# 780-00033_rev_4_486_CCD_Interface.net
KiCad netlist of a schematic drawn in Altium Designer
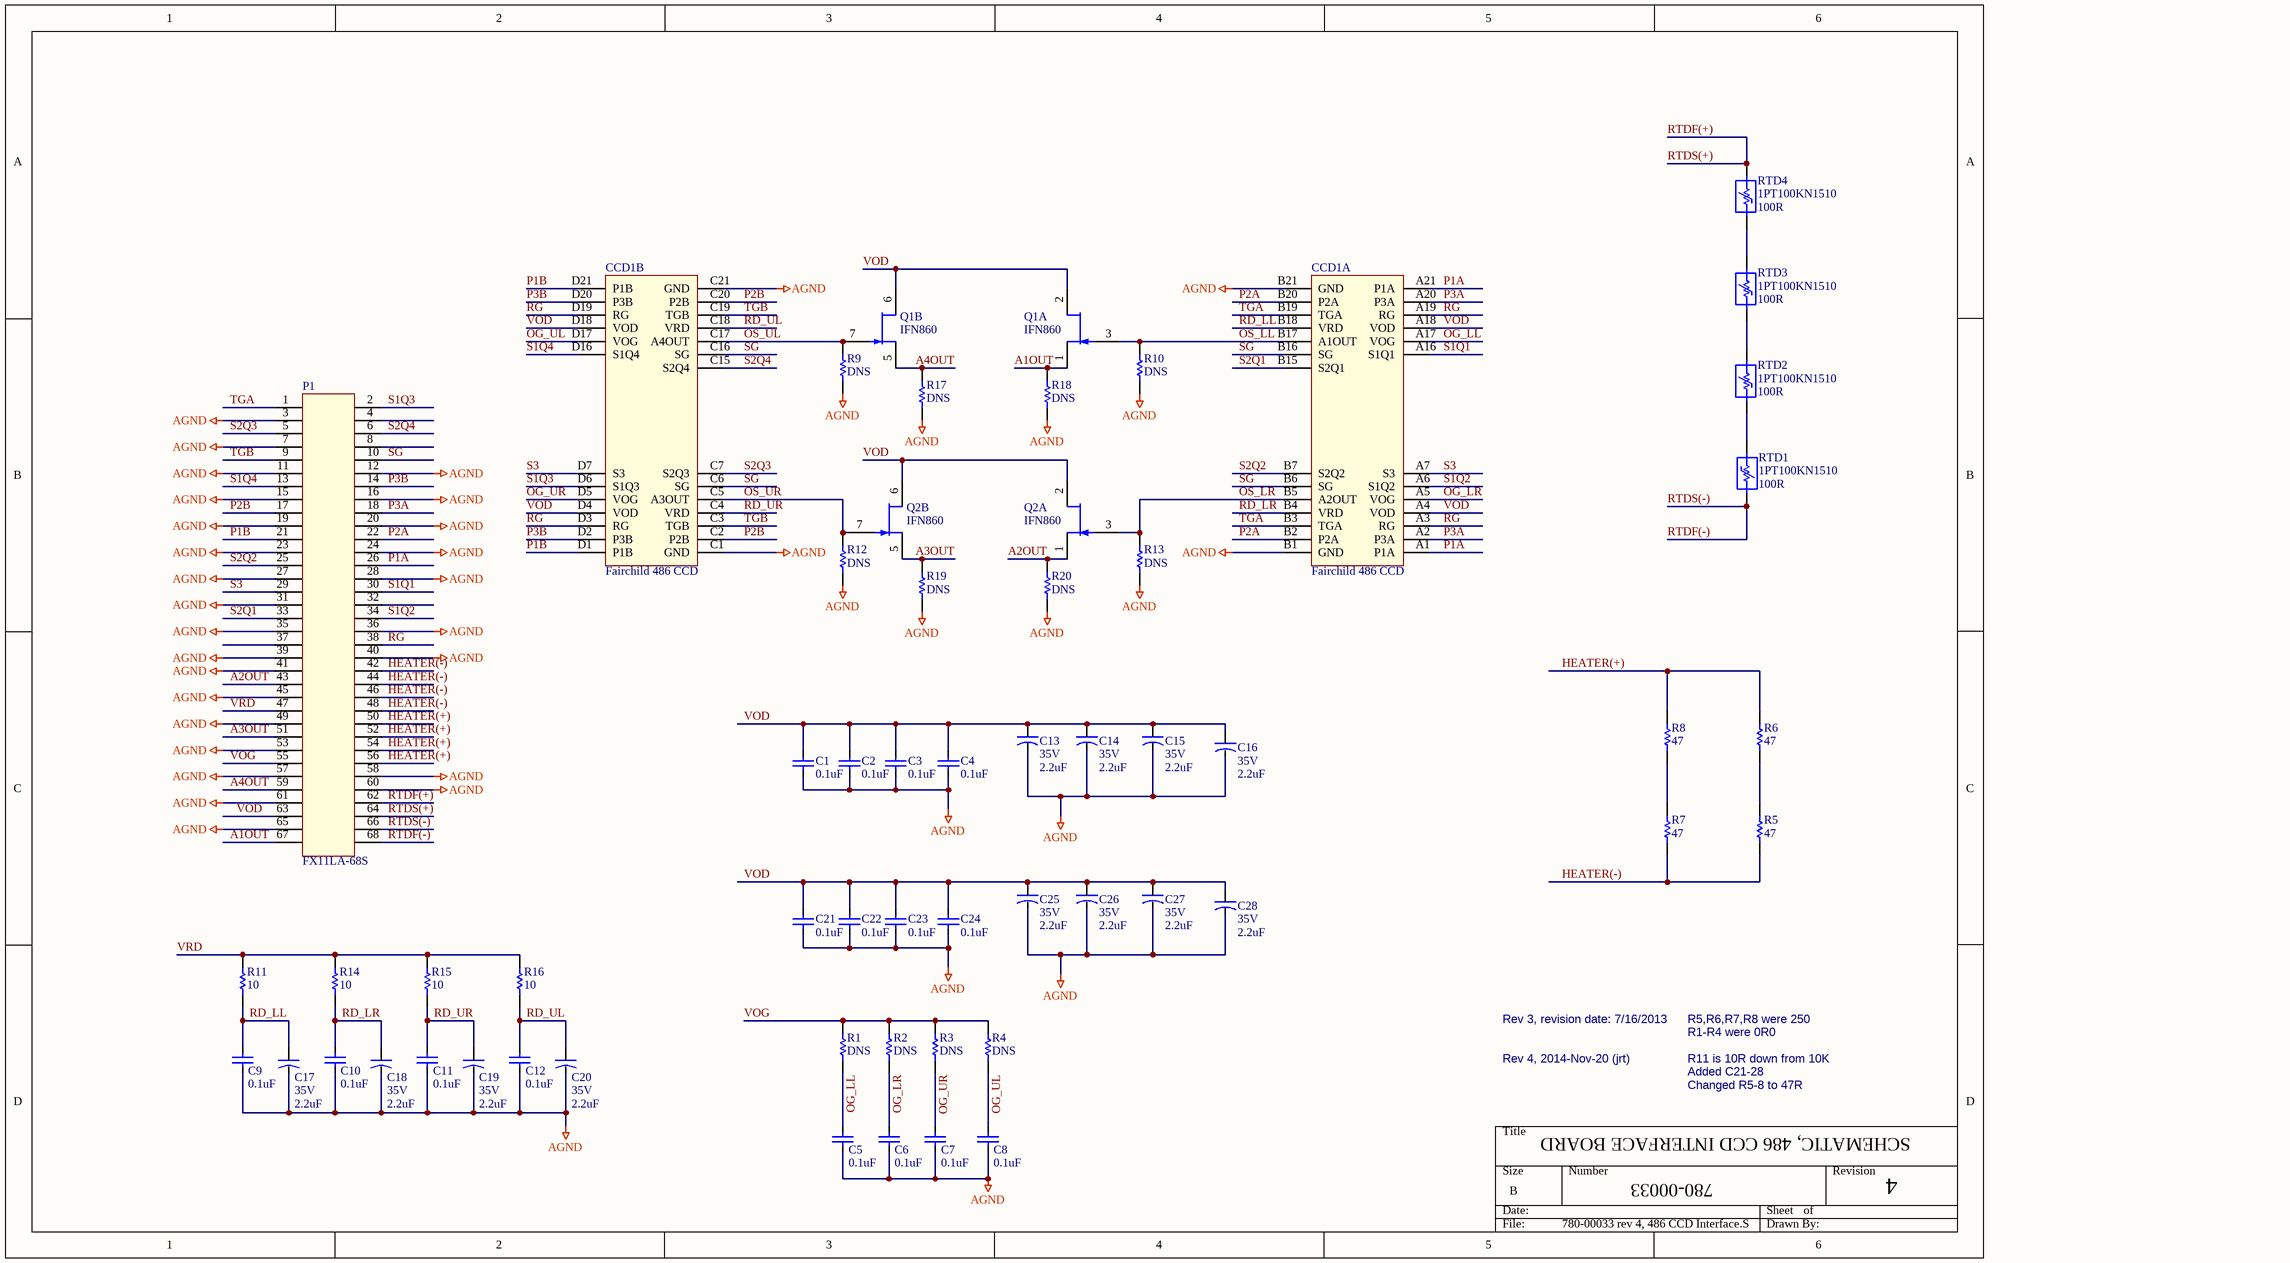
[diagram p0: 780-00033 rev 4, 486 CCD Interface.SchDoc]

(export (version "E")
  (design (tool "Eeschema 10.0.6"))
  (components
    (comp (ref "C1")
      (value "0.1uF")
      (footprint "SMD_0805")
      (description "Capacitor")
      (fields (field (name "MANUFACTURER") "AVX") (field (name "Comment") "Cap SMD"))
      (libsource (lib "175-00029, rev3, 486 CCD Interface") (part "Cap SMD"))
    )
    (comp (ref "C2")
      (value "0.1uF")
      (footprint "SMD_0805")
      (description "Capacitor")
      (fields (field (name "MANUFACTURER") "AVX") (field (name "Comment") "Cap SMD"))
      (libsource (lib "175-00029, rev3, 486 CCD Interface") (part "Cap SMD"))
    )
    (comp (ref "C3")
      (value "0.1uF")
      (footprint "SMD_0805")
      (description "Capacitor")
      (fields (field (name "MANUFACTURER") "AVX") (field (name "Comment") "Cap SMD"))
      (libsource (lib "175-00029, rev3, 486 CCD Interface") (part "Cap SMD"))
    )
    (comp (ref "C4")
      (value "0.1uF")
      (footprint "SMD_0805")
      (description "Capacitor")
      (fields (field (name "MANUFACTURER") "AVX") (field (name "Comment") "Cap SMD"))
      (libsource (lib "175-00029, rev3, 486 CCD Interface") (part "Cap SMD"))
    )
    (comp (ref "C5")
      (value "0.1uF")
      (footprint "SMD_0805")
      (description "Capacitor")
      (fields (field (name "MANUFACTURER") "AVX") (field (name "Comment") "Cap SMD"))
      (libsource (lib "175-00029, rev3, 486 CCD Interface") (part "Cap SMD"))
    )
    (comp (ref "C6")
      (value "0.1uF")
      (footprint "SMD_0805")
      (description "Capacitor")
      (fields (field (name "MANUFACTURER") "AVX") (field (name "Comment") "Cap SMD"))
      (libsource (lib "175-00029, rev3, 486 CCD Interface") (part "Cap SMD"))
    )
    (comp (ref "C7")
      (value "0.1uF")
      (footprint "SMD_0805")
      (description "Capacitor")
      (fields (field (name "MANUFACTURER") "AVX") (field (name "Comment") "Cap SMD"))
      (libsource (lib "175-00029, rev3, 486 CCD Interface") (part "Cap SMD"))
    )
    (comp (ref "C8")
      (value "0.1uF")
      (footprint "SMD_0805")
      (description "Capacitor")
      (fields (field (name "MANUFACTURER") "AVX") (field (name "Comment") "Cap SMD"))
      (libsource (lib "175-00029, rev3, 486 CCD Interface") (part "Cap SMD"))
    )
    (comp (ref "C9")
      (value "0.1uF")
      (footprint "SMD_0805")
      (description "Capacitor")
      (fields (field (name "MANUFACTURER") "AVX") (field (name "Comment") "Cap SMD"))
      (libsource (lib "175-00029, rev3, 486 CCD Interface") (part "Cap SMD"))
    )
    (comp (ref "C10")
      (value "0.1uF")
      (footprint "SMD_0805")
      (description "Capacitor")
      (fields (field (name "MANUFACTURER") "AVX") (field (name "Comment") "Cap SMD"))
      (libsource (lib "175-00029, rev3, 486 CCD Interface") (part "Cap SMD"))
    )
    (comp (ref "C11")
      (value "0.1uF")
      (footprint "SMD_0805")
      (description "Capacitor")
      (fields (field (name "MANUFACTURER") "AVX") (field (name "Comment") "Cap SMD"))
      (libsource (lib "175-00029, rev3, 486 CCD Interface") (part "Cap SMD"))
    )
    (comp (ref "C12")
      (value "0.1uF")
      (footprint "SMD_0805")
      (description "Capacitor")
      (fields (field (name "MANUFACTURER") "AVX") (field (name "Comment") "Cap SMD"))
      (libsource (lib "175-00029, rev3, 486 CCD Interface") (part "Cap SMD"))
    )
    (comp (ref "C13")
      (value "35V")
      (footprint "SMD_CAP_3216")
      (description "outline 3.2mm x 1.6 mm, 1206")
      (fields (field (name "MANUFACTURER") "AVX") (field (name "ALTIUM_VALUE") "2.2uF"))
      (libsource (lib "175-00029, rev3, 486 CCD Interface") (part "Cap 2.2uF 35V Low ESR"))
    )
    (comp (ref "C14")
      (value "35V")
      (footprint "SMD_CAP_3216")
      (description "outline 3.2mm x 1.6 mm, 1206")
      (fields (field (name "MANUFACTURER") "AVX") (field (name "ALTIUM_VALUE") "2.2uF"))
      (libsource (lib "175-00029, rev3, 486 CCD Interface") (part "Cap 2.2uF 35V Low ESR"))
    )
    (comp (ref "C15")
      (value "35V")
      (footprint "SMD_CAP_3216")
      (description "outline 3.2mm x 1.6 mm, 1206")
      (fields (field (name "MANUFACTURER") "AVX") (field (name "ALTIUM_VALUE") "2.2uF"))
      (libsource (lib "175-00029, rev3, 486 CCD Interface") (part "Cap 2.2uF 35V Low ESR"))
    )
    (comp (ref "C16")
      (value "35V")
      (footprint "SMD_CAP_3216")
      (description "outline 3.2mm x 1.6 mm, 1206")
      (fields (field (name "MANUFACTURER") "AVX") (field (name "ALTIUM_VALUE") "2.2uF"))
      (libsource (lib "175-00029, rev3, 486 CCD Interface") (part "Cap 2.2uF 35V Low ESR"))
    )
    (comp (ref "C17")
      (value "35V")
      (footprint "SMD_CAP_3216")
      (description "outline 3.2mm x 1.6 mm, 1206")
      (fields (field (name "MANUFACTURER") "AVX") (field (name "ALTIUM_VALUE") "2.2uF"))
      (libsource (lib "175-00029, rev3, 486 CCD Interface") (part "Cap 2.2uF 35V Low ESR"))
    )
    (comp (ref "C18")
      (value "35V")
      (footprint "SMD_CAP_3216")
      (description "outline 3.2mm x 1.6 mm, 1206")
      (fields (field (name "MANUFACTURER") "AVX") (field (name "ALTIUM_VALUE") "2.2uF"))
      (libsource (lib "175-00029, rev3, 486 CCD Interface") (part "Cap 2.2uF 35V Low ESR"))
    )
    (comp (ref "C19")
      (value "35V")
      (footprint "SMD_CAP_3216")
      (description "outline 3.2mm x 1.6 mm, 1206")
      (fields (field (name "MANUFACTURER") "AVX") (field (name "ALTIUM_VALUE") "2.2uF"))
      (libsource (lib "175-00029, rev3, 486 CCD Interface") (part "Cap 2.2uF 35V Low ESR"))
    )
    (comp (ref "C20")
      (value "35V")
      (footprint "SMD_CAP_3216")
      (description "outline 3.2mm x 1.6 mm, 1206")
      (fields (field (name "MANUFACTURER") "AVX") (field (name "ALTIUM_VALUE") "2.2uF"))
      (libsource (lib "175-00029, rev3, 486 CCD Interface") (part "Cap 2.2uF 35V Low ESR"))
    )
    (comp (ref "C21")
      (value "0.1uF")
      (footprint "SMD_0805")
      (description "Capacitor")
      (fields (field (name "MANUFACTURER") "AVX"))
      (libsource (lib "175-00029, rev3, 486 CCD Interface") (part "Cap SMD"))
    )
    (comp (ref "C22")
      (value "0.1uF")
      (footprint "SMD_0805")
      (description "Capacitor")
      (fields (field (name "MANUFACTURER") "AVX"))
      (libsource (lib "175-00029, rev3, 486 CCD Interface") (part "Cap SMD"))
    )
    (comp (ref "C23")
      (value "0.1uF")
      (footprint "SMD_0805")
      (description "Capacitor")
      (fields (field (name "MANUFACTURER") "AVX") (field (name "Comment") "Cap SMD"))
      (libsource (lib "175-00029, rev3, 486 CCD Interface") (part "Cap SMD"))
    )
    (comp (ref "C24")
      (value "0.1uF")
      (footprint "SMD_0805")
      (description "Capacitor")
      (fields (field (name "MANUFACTURER") "AVX") (field (name "Comment") "Cap SMD"))
      (libsource (lib "175-00029, rev3, 486 CCD Interface") (part "Cap SMD"))
    )
    (comp (ref "C25")
      (value "35V")
      (footprint "SMD_CAP_3216")
      (description "outline 3.2mm x 1.6 mm, 1206")
      (fields (field (name "MANUFACTURER") "AVX") (field (name "ALTIUM_VALUE") "2.2uF"))
      (libsource (lib "175-00029, rev3, 486 CCD Interface") (part "Cap 2.2uF 35V Low ESR"))
    )
    (comp (ref "C26")
      (value "35V")
      (footprint "SMD_CAP_3216")
      (description "outline 3.2mm x 1.6 mm, 1206")
      (fields (field (name "MANUFACTURER") "AVX") (field (name "ALTIUM_VALUE") "2.2uF"))
      (libsource (lib "175-00029, rev3, 486 CCD Interface") (part "Cap 2.2uF 35V Low ESR"))
    )
    (comp (ref "C27")
      (value "35V")
      (footprint "SMD_CAP_3216")
      (description "outline 3.2mm x 1.6 mm, 1206")
      (fields (field (name "MANUFACTURER") "AVX") (field (name "ALTIUM_VALUE") "2.2uF"))
      (libsource (lib "175-00029, rev3, 486 CCD Interface") (part "Cap 2.2uF 35V Low ESR"))
    )
    (comp (ref "C28")
      (value "35V")
      (footprint "SMD_CAP_3216")
      (description "outline 3.2mm x 1.6 mm, 1206")
      (fields (field (name "MANUFACTURER") "AVX") (field (name "ALTIUM_VALUE") "2.2uF"))
      (libsource (lib "175-00029, rev3, 486 CCD Interface") (part "Cap 2.2uF 35V Low ESR"))
    )
    (comp (ref "CCD1")
      (value "Fairchild 486 CCD")
      (footprint "Fairchild 486")
      (libsource (lib "175-00029, rev3, 486 CCD Interface") (part "Fairchild 486 CCD"))
    )
    (comp (ref "P1")
      (value "FX11LA-68S")
      (description "HIROSE 68P Receptacle")
      (fields (field (name "MANUFACTURER") "HiRose"))
      (libsource (lib "175-00029, rev3, 486 CCD Interface") (part "FX11LA-68S"))
    )
    (comp (ref "Q1")
      (value "IFN860")
      (footprint "TO-71")
      (description "N-JFET NJ450L Process")
      (fields (field (name "MANUFACTURER") "INTERFET"))
      (libsource (lib "175-00029, rev3, 486 CCD Interface") (part "IFN860"))
    )
    (comp (ref "Q2")
      (value "IFN860")
      (footprint "TO-71")
      (description "N-JFET NJ450L Process")
      (fields (field (name "MANUFACTURER") "INTERFET"))
      (libsource (lib "175-00029, rev3, 486 CCD Interface") (part "IFN860"))
    )
    (comp (ref "R1")
      (value "DNS")
      (footprint "SMD_0805")
      (description "Resistor 0805")
      (fields (field (name "Comment") "Res SMD"))
      (libsource (lib "175-00029, rev3, 486 CCD Interface") (part "Res SMD"))
    )
    (comp (ref "R2")
      (value "DNS")
      (footprint "SMD_0805")
      (description "Resistor 0805")
      (fields (field (name "Comment") "Res SMD"))
      (libsource (lib "175-00029, rev3, 486 CCD Interface") (part "Res SMD"))
    )
    (comp (ref "R3")
      (value "DNS")
      (footprint "SMD_0805")
      (description "Resistor 0805")
      (fields (field (name "Comment") "Res SMD"))
      (libsource (lib "175-00029, rev3, 486 CCD Interface") (part "Res SMD"))
    )
    (comp (ref "R4")
      (value "DNS")
      (footprint "SMD_0805")
      (description "Resistor 0805")
      (fields (field (name "Comment") "Res SMD"))
      (libsource (lib "175-00029, rev3, 486 CCD Interface") (part "Res SMD"))
    )
    (comp (ref "R5")
      (value "47")
      (footprint "AXIAL-0.5")
      (description "Resistor")
      (fields (field (name "MANUFACTURER") "Vishay/Dale") (field (name "Comment") "Res TH"))
      (libsource (lib "175-00029, rev3, 486 CCD Interface") (part "Res TH"))
    )
    (comp (ref "R6")
      (value "47")
      (footprint "AXIAL-0.5")
      (description "Resistor")
      (fields (field (name "MANUFACTURER") "Vishay/Dale") (field (name "Comment") "Res TH"))
      (libsource (lib "175-00029, rev3, 486 CCD Interface") (part "Res TH"))
    )
    (comp (ref "R7")
      (value "47")
      (footprint "AXIAL-0.5")
      (description "Resistor")
      (fields (field (name "MANUFACTURER") "Vishay/Dale") (field (name "Comment") "Res TH"))
      (libsource (lib "175-00029, rev3, 486 CCD Interface") (part "Res TH"))
    )
    (comp (ref "R8")
      (value "47")
      (footprint "AXIAL-0.5")
      (description "Resistor")
      (fields (field (name "MANUFACTURER") "Vishay/Dale") (field (name "Comment") "Res TH"))
      (libsource (lib "175-00029, rev3, 486 CCD Interface") (part "Res TH"))
    )
    (comp (ref "R9")
      (value "DNS")
      (footprint "SMD_0805")
      (description "Resistor 0805")
      (fields (field (name "Comment") "Res SMD"))
      (libsource (lib "175-00029, rev3, 486 CCD Interface") (part "Res SMD"))
    )
    (comp (ref "R10")
      (value "DNS")
      (footprint "SMD_0805")
      (description "Resistor 0805")
      (fields (field (name "Comment") "Res SMD"))
      (libsource (lib "175-00029, rev3, 486 CCD Interface") (part "Res SMD"))
    )
    (comp (ref "R11")
      (value "10")
      (footprint "SMD_0805")
      (description "Resistor 0805")
      (fields (field (name "Comment") "Res SMD"))
      (libsource (lib "175-00029, rev3, 486 CCD Interface") (part "Res SMD"))
    )
    (comp (ref "R12")
      (value "DNS")
      (footprint "SMD_0805")
      (description "Resistor 0805")
      (fields (field (name "Comment") "Res SMD"))
      (libsource (lib "175-00029, rev3, 486 CCD Interface") (part "Res SMD"))
    )
    (comp (ref "R13")
      (value "DNS")
      (footprint "SMD_0805")
      (description "Resistor 0805")
      (fields (field (name "Comment") "Res SMD"))
      (libsource (lib "175-00029, rev3, 486 CCD Interface") (part "Res SMD"))
    )
    (comp (ref "R14")
      (value "10")
      (footprint "SMD_0805")
      (description "Resistor 0805")
      (fields (field (name "Comment") "Res SMD"))
      (libsource (lib "175-00029, rev3, 486 CCD Interface") (part "Res SMD"))
    )
    (comp (ref "R15")
      (value "10")
      (footprint "SMD_0805")
      (description "Resistor 0805")
      (fields (field (name "Comment") "Res SMD"))
      (libsource (lib "175-00029, rev3, 486 CCD Interface") (part "Res SMD"))
    )
    (comp (ref "R16")
      (value "10")
      (footprint "SMD_0805")
      (description "Resistor 0805")
      (fields (field (name "Comment") "Res SMD"))
      (libsource (lib "175-00029, rev3, 486 CCD Interface") (part "Res SMD"))
    )
    (comp (ref "R17")
      (value "DNS")
      (footprint "SMD_0805")
      (description "Resistor 0805")
      (fields (field (name "Comment") "Res SMD"))
      (libsource (lib "175-00029, rev3, 486 CCD Interface") (part "Res SMD"))
    )
    (comp (ref "R18")
      (value "DNS")
      (footprint "SMD_0805")
      (description "Resistor 0805")
      (fields (field (name "Comment") "Res SMD"))
      (libsource (lib "175-00029, rev3, 486 CCD Interface") (part "Res SMD"))
    )
    (comp (ref "R19")
      (value "DNS")
      (footprint "SMD_0805")
      (description "Resistor 0805")
      (fields (field (name "Comment") "Res SMD"))
      (libsource (lib "175-00029, rev3, 486 CCD Interface") (part "Res SMD"))
    )
    (comp (ref "R20")
      (value "DNS")
      (footprint "SMD_0805")
      (description "Resistor 0805")
      (fields (field (name "Comment") "Res SMD"))
      (libsource (lib "175-00029, rev3, 486 CCD Interface") (part "Res SMD"))
    )
    (comp (ref "RTD1")
      (value "100R")
      (footprint "RTD 1x15mm")
      (description "Pt RTD")
      (fields
        (field (name "MANUFACTURER") "OMEGA")
        (field (name "MANUF P/N") "1PT100KN1510")
        (field (name "Comment") "RTD 2-wire, 1x15mm")
      )
      (libsource (lib "175-00029, rev3, 486 CCD Interface") (part "RTD 2-wire, 1x15mm"))
    )
    (comp (ref "RTD2")
      (value "100R")
      (footprint "RTD 1x15mm")
      (description "Pt RTD")
      (fields
        (field (name "MANUFACTURER") "OMEGA")
        (field (name "MANUF P/N") "1PT100KN1510")
        (field (name "Comment") "RTD 2-wire, 1x15mm")
      )
      (libsource (lib "175-00029, rev3, 486 CCD Interface") (part "RTD 2-wire, 1x15mm"))
    )
    (comp (ref "RTD3")
      (value "100R")
      (footprint "RTD 1x15mm")
      (description "Pt RTD")
      (fields
        (field (name "MANUFACTURER") "OMEGA")
        (field (name "MANUF P/N") "1PT100KN1510")
        (field (name "Comment") "RTD 2-wire, 1x15mm")
      )
      (libsource (lib "175-00029, rev3, 486 CCD Interface") (part "RTD 2-wire, 1x15mm"))
    )
    (comp (ref "RTD4")
      (value "100R")
      (footprint "RTD 1x15mm")
      (description "Pt RTD")
      (fields
        (field (name "MANUFACTURER") "OMEGA")
        (field (name "MANUF P/N") "1PT100KN1510")
        (field (name "Comment") "RTD 2-wire, 1x15mm")
      )
      (libsource (lib "175-00029, rev3, 486 CCD Interface") (part "RTD 2-wire, 1x15mm"))
    )
  )
  (nets
    (net (code "1") (name "/A1OUT") (class "Default")
      (node (ref "P1") (pin "67") (pintype "passive"))
      (node (ref "Q1") (pin "1") (pinfunction "S_1") (pintype "passive"))
      (node (ref "R18") (pin "1") (pinfunction "1_1") (pintype "passive"))
    )
    (net (code "2") (name "/A2OUT") (class "Default")
      (node (ref "P1") (pin "43") (pintype "passive"))
      (node (ref "Q2") (pin "1") (pinfunction "S_1") (pintype "passive"))
      (node (ref "R20") (pin "1") (pinfunction "1_1") (pintype "passive"))
    )
    (net (code "3") (name "/A3OUT") (class "Default")
      (node (ref "P1") (pin "51") (pintype "passive"))
      (node (ref "Q2") (pin "5") (pinfunction "S_5") (pintype "passive"))
      (node (ref "R19") (pin "1") (pinfunction "1_1") (pintype "passive"))
    )
    (net (code "4") (name "/A4OUT") (class "Default")
      (node (ref "P1") (pin "59") (pintype "passive"))
      (node (ref "Q1") (pin "5") (pinfunction "S_5") (pintype "passive"))
      (node (ref "R17") (pin "1") (pinfunction "1_1") (pintype "passive"))
    )
    (net (code "5") (name "/HEATER(+)") (class "Default")
      (node (ref "P1") (pin "50") (pintype "passive"))
      (node (ref "P1") (pin "52") (pintype "passive"))
      (node (ref "P1") (pin "54") (pintype "passive"))
      (node (ref "P1") (pin "56") (pintype "passive"))
      (node (ref "R6") (pin "1") (pinfunction "1_1") (pintype "passive"))
      (node (ref "R8") (pin "2") (pinfunction "2_2") (pintype "passive"))
    )
    (net (code "6") (name "/HEATER(-)") (class "Default")
      (node (ref "P1") (pin "42") (pintype "passive"))
      (node (ref "P1") (pin "44") (pintype "passive"))
      (node (ref "P1") (pin "46") (pintype "passive"))
      (node (ref "P1") (pin "48") (pintype "passive"))
      (node (ref "R5") (pin "1") (pinfunction "1_1") (pintype "passive"))
      (node (ref "R7") (pin "2") (pinfunction "2_2") (pintype "passive"))
    )
    (net (code "7") (name "/OG_LL") (class "Default")
      (node (ref "C5") (pin "2") (pinfunction "2_2") (pintype "passive"))
      (node (ref "CCD1") (pin "A17") (pinfunction "VOG_A17") (pintype "passive"))
      (node (ref "R1") (pin "1") (pinfunction "1_1") (pintype "passive"))
    )
    (net (code "8") (name "/OG_LR") (class "Default")
      (node (ref "C6") (pin "2") (pinfunction "2_2") (pintype "passive"))
      (node (ref "CCD1") (pin "A5") (pinfunction "VOG_A5") (pintype "passive"))
      (node (ref "R2") (pin "1") (pinfunction "1_1") (pintype "passive"))
    )
    (net (code "9") (name "/OG_UL") (class "Default")
      (node (ref "C8") (pin "2") (pinfunction "2_2") (pintype "passive"))
      (node (ref "CCD1") (pin "D17") (pinfunction "VOG_D17") (pintype "passive"))
      (node (ref "R4") (pin "1") (pinfunction "1_1") (pintype "passive"))
    )
    (net (code "10") (name "/OG_UR") (class "Default")
      (node (ref "C7") (pin "2") (pinfunction "2_2") (pintype "passive"))
      (node (ref "CCD1") (pin "D5") (pinfunction "VOG_D5") (pintype "passive"))
      (node (ref "R3") (pin "1") (pinfunction "1_1") (pintype "passive"))
    )
    (net (code "11") (name "/OS_LL") (class "Default")
      (node (ref "CCD1") (pin "B17") (pinfunction "A1OUT_B17") (pintype "passive"))
      (node (ref "Q1") (pin "3") (pinfunction "G_3") (pintype "passive"))
      (node (ref "R10") (pin "2") (pinfunction "2_2") (pintype "passive"))
    )
    (net (code "12") (name "/OS_LR") (class "Default")
      (node (ref "CCD1") (pin "B5") (pinfunction "A2OUT_B5") (pintype "passive"))
      (node (ref "Q2") (pin "3") (pinfunction "G_3") (pintype "passive"))
      (node (ref "R13") (pin "2") (pinfunction "2_2") (pintype "passive"))
    )
    (net (code "13") (name "/OS_UL") (class "Default")
      (node (ref "CCD1") (pin "C17") (pinfunction "A4OUT_C17") (pintype "passive"))
      (node (ref "Q1") (pin "7") (pinfunction "G_7") (pintype "passive"))
      (node (ref "R9") (pin "2") (pinfunction "2_2") (pintype "passive"))
    )
    (net (code "14") (name "/OS_UR") (class "Default")
      (node (ref "CCD1") (pin "C5") (pinfunction "A3OUT_C5") (pintype "passive"))
      (node (ref "Q2") (pin "7") (pinfunction "G_7") (pintype "passive"))
      (node (ref "R12") (pin "2") (pinfunction "2_2") (pintype "passive"))
    )
    (net (code "15") (name "/P1A") (class "Default")
      (node (ref "CCD1") (pin "A1") (pinfunction "P1A_A1") (pintype "passive"))
      (node (ref "CCD1") (pin "A21") (pinfunction "P1A_A21") (pintype "passive"))
      (node (ref "P1") (pin "26") (pintype "passive"))
    )
    (net (code "16") (name "/P1B") (class "Default")
      (node (ref "CCD1") (pin "D1") (pinfunction "P1B_D1") (pintype "passive"))
      (node (ref "CCD1") (pin "D21") (pinfunction "P1B_D21") (pintype "passive"))
      (node (ref "P1") (pin "21") (pintype "passive"))
    )
    (net (code "17") (name "/P2A") (class "Default")
      (node (ref "CCD1") (pin "B2") (pinfunction "P2A_B2") (pintype "passive"))
      (node (ref "CCD1") (pin "B20") (pinfunction "P2A_B20") (pintype "passive"))
      (node (ref "P1") (pin "22") (pintype "passive"))
    )
    (net (code "18") (name "/P2B") (class "Default")
      (node (ref "CCD1") (pin "C2") (pinfunction "P2B_C2") (pintype "passive"))
      (node (ref "CCD1") (pin "C20") (pinfunction "P2B_C20") (pintype "passive"))
      (node (ref "P1") (pin "17") (pintype "passive"))
    )
    (net (code "19") (name "/P3A") (class "Default")
      (node (ref "CCD1") (pin "A2") (pinfunction "P3A_A2") (pintype "passive"))
      (node (ref "CCD1") (pin "A20") (pinfunction "P3A_A20") (pintype "passive"))
      (node (ref "P1") (pin "18") (pintype "passive"))
    )
    (net (code "20") (name "/P3B") (class "Default")
      (node (ref "CCD1") (pin "D2") (pinfunction "P3B_D2") (pintype "passive"))
      (node (ref "CCD1") (pin "D20") (pinfunction "P3B_D20") (pintype "passive"))
      (node (ref "P1") (pin "14") (pintype "passive"))
    )
    (net (code "21") (name "/RD_LL") (class "Default")
      (node (ref "C17") (pin "1") (pinfunction "1_1") (pintype "passive"))
      (node (ref "C9") (pin "2") (pinfunction "2_2") (pintype "passive"))
      (node (ref "CCD1") (pin "B18") (pinfunction "VRD_B18") (pintype "passive"))
      (node (ref "R11") (pin "2") (pinfunction "2_2") (pintype "passive"))
    )
    (net (code "22") (name "/RD_LR") (class "Default")
      (node (ref "C10") (pin "2") (pinfunction "2_2") (pintype "passive"))
      (node (ref "C18") (pin "1") (pinfunction "1_1") (pintype "passive"))
      (node (ref "CCD1") (pin "B4") (pinfunction "VRD_B4") (pintype "passive"))
      (node (ref "R14") (pin "2") (pinfunction "2_2") (pintype "passive"))
    )
    (net (code "23") (name "/RD_UL") (class "Default")
      (node (ref "C12") (pin "2") (pinfunction "2_2") (pintype "passive"))
      (node (ref "C20") (pin "1") (pinfunction "1_1") (pintype "passive"))
      (node (ref "CCD1") (pin "C18") (pinfunction "VRD_C18") (pintype "passive"))
      (node (ref "R16") (pin "2") (pinfunction "2_2") (pintype "passive"))
    )
    (net (code "24") (name "/RD_UR") (class "Default")
      (node (ref "C11") (pin "2") (pinfunction "2_2") (pintype "passive"))
      (node (ref "C19") (pin "1") (pinfunction "1_1") (pintype "passive"))
      (node (ref "CCD1") (pin "C4") (pinfunction "VRD_C4") (pintype "passive"))
      (node (ref "R15") (pin "2") (pinfunction "2_2") (pintype "passive"))
    )
    (net (code "25") (name "/RG") (class "Default")
      (node (ref "CCD1") (pin "A19") (pinfunction "RG_A19") (pintype "passive"))
      (node (ref "CCD1") (pin "A3") (pinfunction "RG_A3") (pintype "passive"))
      (node (ref "CCD1") (pin "D19") (pinfunction "RG_D19") (pintype "passive"))
      (node (ref "CCD1") (pin "D3") (pinfunction "RG_D3") (pintype "passive"))
      (node (ref "P1") (pin "38") (pintype "passive"))
    )
    (net (code "26") (name "/RTDF(+)") (class "Default")
      (node (ref "P1") (pin "62") (pintype "passive"))
      (node (ref "P1") (pin "64") (pintype "passive"))
      (node (ref "RTD4") (pin "2") (pinfunction "2_2") (pintype "passive"))
    )
    (net (code "27") (name "/RTDF(-)") (class "Default")
      (node (ref "P1") (pin "66") (pintype "passive"))
      (node (ref "P1") (pin "68") (pintype "passive"))
      (node (ref "RTD1") (pin "2") (pinfunction "2_2") (pintype "passive"))
    )
    (net (code "28") (name "/S1Q1") (class "Default")
      (node (ref "CCD1") (pin "A16") (pinfunction "S1Q1_A16") (pintype "passive"))
      (node (ref "P1") (pin "30") (pintype "passive"))
    )
    (net (code "29") (name "/S1Q2") (class "Default")
      (node (ref "CCD1") (pin "A6") (pinfunction "S1Q2_A6") (pintype "passive"))
      (node (ref "P1") (pin "34") (pintype "passive"))
    )
    (net (code "30") (name "/S1Q3") (class "Default")
      (node (ref "CCD1") (pin "D6") (pinfunction "S1Q3_D6") (pintype "passive"))
      (node (ref "P1") (pin "2") (pintype "passive"))
    )
    (net (code "31") (name "/S1Q4") (class "Default")
      (node (ref "CCD1") (pin "D16") (pinfunction "S1Q4_D16") (pintype "passive"))
      (node (ref "P1") (pin "13") (pintype "passive"))
    )
    (net (code "32") (name "/S2Q1") (class "Default")
      (node (ref "CCD1") (pin "B15") (pinfunction "S2Q1_B15") (pintype "passive"))
      (node (ref "P1") (pin "33") (pintype "passive"))
    )
    (net (code "33") (name "/S2Q2") (class "Default")
      (node (ref "CCD1") (pin "B7") (pinfunction "S2Q2_B7") (pintype "passive"))
      (node (ref "P1") (pin "25") (pintype "passive"))
    )
    (net (code "34") (name "/S2Q3") (class "Default")
      (node (ref "CCD1") (pin "C7") (pinfunction "S2Q3_C7") (pintype "passive"))
      (node (ref "P1") (pin "5") (pintype "passive"))
    )
    (net (code "35") (name "/S2Q4") (class "Default")
      (node (ref "CCD1") (pin "C15") (pinfunction "S2Q4_C15") (pintype "passive"))
      (node (ref "P1") (pin "6") (pintype "passive"))
    )
    (net (code "36") (name "/S3") (class "Default")
      (node (ref "CCD1") (pin "A7") (pinfunction "S3_A7") (pintype "passive"))
      (node (ref "CCD1") (pin "D7") (pinfunction "S3_D7") (pintype "passive"))
      (node (ref "P1") (pin "29") (pintype "passive"))
    )
    (net (code "37") (name "/SG") (class "Default")
      (node (ref "CCD1") (pin "B16") (pinfunction "SG_B16") (pintype "passive"))
      (node (ref "CCD1") (pin "B6") (pinfunction "SG_B6") (pintype "passive"))
      (node (ref "CCD1") (pin "C16") (pinfunction "SG_C16") (pintype "passive"))
      (node (ref "CCD1") (pin "C6") (pinfunction "SG_C6") (pintype "passive"))
      (node (ref "P1") (pin "10") (pintype "passive"))
    )
    (net (code "38") (name "/TGA") (class "Default")
      (node (ref "CCD1") (pin "B19") (pinfunction "TGA_B19") (pintype "passive"))
      (node (ref "CCD1") (pin "B3") (pinfunction "TGA_B3") (pintype "passive"))
      (node (ref "P1") (pin "1") (pintype "passive"))
    )
    (net (code "39") (name "/TGB") (class "Default")
      (node (ref "CCD1") (pin "C19") (pinfunction "TGB_C19") (pintype "passive"))
      (node (ref "CCD1") (pin "C3") (pinfunction "TGB_C3") (pintype "passive"))
      (node (ref "P1") (pin "9") (pintype "passive"))
    )
    (net (code "40") (name "/VOD") (class "Default")
      (node (ref "C1") (pin "2") (pinfunction "2_2") (pintype "passive"))
      (node (ref "C13") (pin "1") (pinfunction "1_1") (pintype "passive"))
      (node (ref "C14") (pin "1") (pinfunction "1_1") (pintype "passive"))
      (node (ref "C15") (pin "1") (pinfunction "1_1") (pintype "passive"))
      (node (ref "C16") (pin "1") (pinfunction "1_1") (pintype "passive"))
      (node (ref "C2") (pin "2") (pinfunction "2_2") (pintype "passive"))
      (node (ref "C21") (pin "2") (pinfunction "2_2") (pintype "passive"))
      (node (ref "C22") (pin "2") (pinfunction "2_2") (pintype "passive"))
      (node (ref "C23") (pin "2") (pinfunction "2_2") (pintype "passive"))
      (node (ref "C24") (pin "2") (pinfunction "2_2") (pintype "passive"))
      (node (ref "C25") (pin "1") (pinfunction "1_1") (pintype "passive"))
      (node (ref "C26") (pin "1") (pinfunction "1_1") (pintype "passive"))
      (node (ref "C27") (pin "1") (pinfunction "1_1") (pintype "passive"))
      (node (ref "C28") (pin "1") (pinfunction "1_1") (pintype "passive"))
      (node (ref "C3") (pin "2") (pinfunction "2_2") (pintype "passive"))
      (node (ref "C4") (pin "2") (pinfunction "2_2") (pintype "passive"))
      (node (ref "CCD1") (pin "A18") (pinfunction "VOD_A18") (pintype "passive"))
      (node (ref "CCD1") (pin "A4") (pinfunction "VOD_A4") (pintype "passive"))
      (node (ref "CCD1") (pin "D18") (pinfunction "VOD_D18") (pintype "passive"))
      (node (ref "CCD1") (pin "D4") (pinfunction "VOD_D4") (pintype "passive"))
      (node (ref "P1") (pin "63") (pintype "passive"))
      (node (ref "Q1") (pin "2") (pinfunction "D_2") (pintype "passive"))
      (node (ref "Q1") (pin "6") (pinfunction "D_6") (pintype "passive"))
      (node (ref "Q2") (pin "2") (pinfunction "D_2") (pintype "passive"))
      (node (ref "Q2") (pin "6") (pinfunction "D_6") (pintype "passive"))
    )
    (net (code "41") (name "/VOG") (class "Default")
      (node (ref "P1") (pin "55") (pintype "passive"))
      (node (ref "R1") (pin "2") (pinfunction "2_2") (pintype "passive"))
      (node (ref "R2") (pin "2") (pinfunction "2_2") (pintype "passive"))
      (node (ref "R3") (pin "2") (pinfunction "2_2") (pintype "passive"))
      (node (ref "R4") (pin "2") (pinfunction "2_2") (pintype "passive"))
    )
    (net (code "42") (name "/VRD") (class "Default")
      (node (ref "P1") (pin "47") (pintype "passive"))
      (node (ref "R11") (pin "1") (pinfunction "1_1") (pintype "passive"))
      (node (ref "R14") (pin "1") (pinfunction "1_1") (pintype "passive"))
      (node (ref "R15") (pin "1") (pinfunction "1_1") (pintype "passive"))
      (node (ref "R16") (pin "1") (pinfunction "1_1") (pintype "passive"))
    )
    (net (code "43") (name "AGND") (class "Default")
      (node (ref "C1") (pin "1") (pinfunction "1_1") (pintype "passive"))
      (node (ref "C10") (pin "1") (pinfunction "1_1") (pintype "passive"))
      (node (ref "C11") (pin "1") (pinfunction "1_1") (pintype "passive"))
      (node (ref "C12") (pin "1") (pinfunction "1_1") (pintype "passive"))
      (node (ref "C13") (pin "2") (pinfunction "2_2") (pintype "passive"))
      (node (ref "C14") (pin "2") (pinfunction "2_2") (pintype "passive"))
      (node (ref "C15") (pin "2") (pinfunction "2_2") (pintype "passive"))
      (node (ref "C16") (pin "2") (pinfunction "2_2") (pintype "passive"))
      (node (ref "C17") (pin "2") (pinfunction "2_2") (pintype "passive"))
      (node (ref "C18") (pin "2") (pinfunction "2_2") (pintype "passive"))
      (node (ref "C19") (pin "2") (pinfunction "2_2") (pintype "passive"))
      (node (ref "C2") (pin "1") (pinfunction "1_1") (pintype "passive"))
      (node (ref "C20") (pin "2") (pinfunction "2_2") (pintype "passive"))
      (node (ref "C21") (pin "1") (pinfunction "1_1") (pintype "passive"))
      (node (ref "C22") (pin "1") (pinfunction "1_1") (pintype "passive"))
      (node (ref "C23") (pin "1") (pinfunction "1_1") (pintype "passive"))
      (node (ref "C24") (pin "1") (pinfunction "1_1") (pintype "passive"))
      (node (ref "C25") (pin "2") (pinfunction "2_2") (pintype "passive"))
      (node (ref "C26") (pin "2") (pinfunction "2_2") (pintype "passive"))
      (node (ref "C27") (pin "2") (pinfunction "2_2") (pintype "passive"))
      (node (ref "C28") (pin "2") (pinfunction "2_2") (pintype "passive"))
      (node (ref "C3") (pin "1") (pinfunction "1_1") (pintype "passive"))
      (node (ref "C4") (pin "1") (pinfunction "1_1") (pintype "passive"))
      (node (ref "C5") (pin "1") (pinfunction "1_1") (pintype "passive"))
      (node (ref "C6") (pin "1") (pinfunction "1_1") (pintype "passive"))
      (node (ref "C7") (pin "1") (pinfunction "1_1") (pintype "passive"))
      (node (ref "C8") (pin "1") (pinfunction "1_1") (pintype "passive"))
      (node (ref "C9") (pin "1") (pinfunction "1_1") (pintype "passive"))
      (node (ref "CCD1") (pin "B1") (pinfunction "GND_B1") (pintype "passive"))
      (node (ref "CCD1") (pin "B21") (pinfunction "GND_B21") (pintype "passive"))
      (node (ref "CCD1") (pin "C1") (pinfunction "GND_C1") (pintype "passive"))
      (node (ref "CCD1") (pin "C21") (pinfunction "GND_C21") (pintype "passive"))
      (node (ref "P1") (pin "11") (pintype "passive"))
      (node (ref "P1") (pin "12") (pintype "passive"))
      (node (ref "P1") (pin "15") (pintype "passive"))
      (node (ref "P1") (pin "16") (pintype "passive"))
      (node (ref "P1") (pin "19") (pintype "passive"))
      (node (ref "P1") (pin "20") (pintype "passive"))
      (node (ref "P1") (pin "23") (pintype "passive"))
      (node (ref "P1") (pin "24") (pintype "passive"))
      (node (ref "P1") (pin "27") (pintype "passive"))
      (node (ref "P1") (pin "28") (pintype "passive"))
      (node (ref "P1") (pin "3") (pintype "passive"))
      (node (ref "P1") (pin "31") (pintype "passive"))
      (node (ref "P1") (pin "35") (pintype "passive"))
      (node (ref "P1") (pin "36") (pintype "passive"))
      (node (ref "P1") (pin "39") (pintype "passive"))
      (node (ref "P1") (pin "40") (pintype "passive"))
      (node (ref "P1") (pin "41") (pintype "passive"))
      (node (ref "P1") (pin "45") (pintype "passive"))
      (node (ref "P1") (pin "49") (pintype "passive"))
      (node (ref "P1") (pin "53") (pintype "passive"))
      (node (ref "P1") (pin "57") (pintype "passive"))
      (node (ref "P1") (pin "58") (pintype "passive"))
      (node (ref "P1") (pin "60") (pintype "passive"))
      (node (ref "P1") (pin "61") (pintype "passive"))
      (node (ref "P1") (pin "65") (pintype "passive"))
      (node (ref "P1") (pin "7") (pintype "passive"))
      (node (ref "R10") (pin "1") (pinfunction "1_1") (pintype "passive"))
      (node (ref "R12") (pin "1") (pinfunction "1_1") (pintype "passive"))
      (node (ref "R13") (pin "1") (pinfunction "1_1") (pintype "passive"))
      (node (ref "R17") (pin "2") (pinfunction "2_2") (pintype "passive"))
      (node (ref "R18") (pin "2") (pinfunction "2_2") (pintype "passive"))
      (node (ref "R19") (pin "2") (pinfunction "2_2") (pintype "passive"))
      (node (ref "R20") (pin "2") (pinfunction "2_2") (pintype "passive"))
      (node (ref "R9") (pin "1") (pinfunction "1_1") (pintype "passive"))
    )
    (net (code "44") (name "Net-(R5-Pad2)") (class "Default")
      (node (ref "R5") (pin "2") (pinfunction "2_2") (pintype "passive"))
      (node (ref "R6") (pin "2") (pinfunction "2_2") (pintype "passive"))
    )
    (net (code "45") (name "Net-(R7-Pad1)") (class "Default")
      (node (ref "R7") (pin "1") (pinfunction "1_1") (pintype "passive"))
      (node (ref "R8") (pin "1") (pinfunction "1_1") (pintype "passive"))
    )
    (net (code "46") (name "Net-(RTD1-Pad1)") (class "Default")
      (node (ref "RTD1") (pin "1") (pinfunction "1_1") (pintype "passive"))
      (node (ref "RTD2") (pin "1") (pinfunction "1_1") (pintype "passive"))
    )
    (net (code "47") (name "Net-(RTD2-Pad2)") (class "Default")
      (node (ref "RTD2") (pin "2") (pinfunction "2_2") (pintype "passive"))
      (node (ref "RTD3") (pin "1") (pinfunction "1_1") (pintype "passive"))
    )
    (net (code "48") (name "Net-(RTD3-Pad2)") (class "Default")
      (node (ref "RTD3") (pin "2") (pinfunction "2_2") (pintype "passive"))
      (node (ref "RTD4") (pin "1") (pinfunction "1_1") (pintype "passive"))
    )
    (net (code "49") (name "unconnected-(P1-Pad4)") (class "Default")
      (node (ref "P1") (pin "4") (pintype "passive"))
    )
    (net (code "50") (name "unconnected-(P1-Pad8)") (class "Default")
      (node (ref "P1") (pin "8") (pintype "passive"))
    )
    (net (code "51") (name "unconnected-(P1-Pad32)") (class "Default")
      (node (ref "P1") (pin "32") (pintype "passive"))
    )
    (net (code "52") (name "unconnected-(P1-Pad37)") (class "Default")
      (node (ref "P1") (pin "37") (pintype "passive"))
    )
  )
)
